# Board2.net
KiCad netlist of a schematic drawn in EAGLE
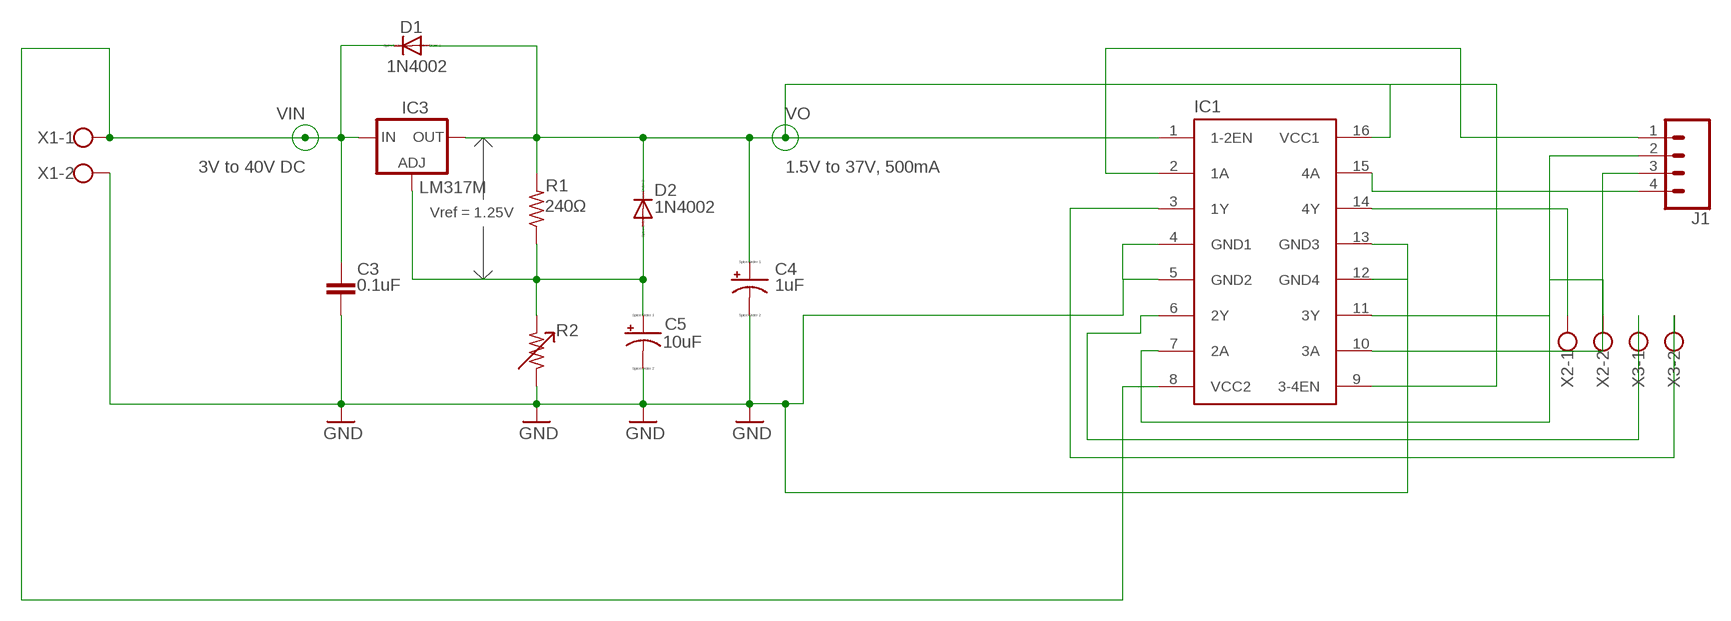
[diagram p0: schematic, sheet 1]

(export (version "E")
  (design (tool "Eeschema 10.0.6"))
  (components
    (comp (ref "C3")
      (value "0.1uF")
      (footprint "eagle-import:C075-052X106")
      (libsource (lib "eagle-import") (part "C-EU075-052X106"))
    )
    (comp (ref "C4")
      (value "1uF")
      (footprint "eagle-import:085CS_1AR")
      (libsource (lib "eagle-import") (part "CPOL-US085CS-1AR"))
    )
    (comp (ref "C5")
      (value "10uF")
      (footprint "eagle-import:085CS_1AR")
      (libsource (lib "eagle-import") (part "CPOL-US085CS-1AR"))
    )
    (comp (ref "D1")
      (value "1N4002")
      (footprint "eagle-import:DO41-10")
      (libsource (lib "eagle-import") (part "1N4004"))
    )
    (comp (ref "D2")
      (value "1N4002")
      (footprint "eagle-import:DO41-10")
      (libsource (lib "eagle-import") (part "1N4004"))
    )
    (comp (ref "IC1")
      (value "L293D")
      (footprint "eagle-import:DIL16")
      (libsource (lib "eagle-import") (part "L293D"))
    )
    (comp (ref "IC3")
      (value "LM317MBSTT3")
      (footprint "eagle-import:SOT223")
      (fields (field (name "PARTNUMBER") "LM317M"))
      (libsource (lib "eagle-import") (part "LM317?MBSTT3"))
    )
    (comp (ref "J1")
      (value "CONN_04PTH")
      (footprint "eagle-import:1X04")
      (libsource (lib "eagle-import") (part "CONN_04PTH"))
    )
    (comp (ref "R1")
      (value "240Ω")
      (footprint "eagle-import:M0805")
      (libsource (lib "eagle-import") (part "R-US_M0805"))
    )
    (comp (ref "R2")
      (value "RESISTOR_TRIMR0805")
      (footprint "eagle-import:R0805")
      (libsource (lib "eagle-import") (part "RESISTOR_TRIMR0805"))
    )
    (comp (ref "X1")
      (value "W237-102")
      (footprint "eagle-import:W237-102")
      (fields (field (name "MPN") "237-102"))
      (libsource (lib "eagle-import") (part "W237-102"))
    )
    (comp (ref "X2")
      (value "W237-102")
      (footprint "eagle-import:W237-102")
      (fields (field (name "MPN") "237-102"))
      (libsource (lib "eagle-import") (part "W237-102"))
    )
    (comp (ref "X3")
      (value "W237-102")
      (footprint "eagle-import:W237-102")
      (fields (field (name "MPN") "237-102"))
      (libsource (lib "eagle-import") (part "W237-102"))
    )
  )
  (nets
    (net (code "1") (name "/VIN") (class "Default")
      (node (ref "C3") (pin "1") (pinfunction "1_1") (pintype "passive"))
      (node (ref "D1") (pin "C") (pinfunction "C_C") (pintype "passive"))
      (node (ref "IC1") (pin "8") (pinfunction "VCC2_8") (pintype "power_in"))
      (node (ref "IC3") (pin "3") (pinfunction "IN_3") (pintype "input"))
      (node (ref "X1") (pin "1") (pinfunction "KL_1") (pintype "passive"))
    )
    (net (code "2") (name "/VO") (class "Default")
      (node (ref "C4") (pin "+") (pinfunction "+_+") (pintype "passive"))
      (node (ref "D1") (pin "A") (pinfunction "A_A") (pintype "passive"))
      (node (ref "D2") (pin "C") (pinfunction "C_C") (pintype "passive"))
      (node (ref "IC1") (pin "1") (pinfunction "1-2EN_1") (pintype "input"))
      (node (ref "IC1") (pin "16") (pinfunction "VCC1_16") (pintype "power_in"))
      (node (ref "IC1") (pin "9") (pinfunction "3-4EN_9") (pintype "input"))
      (node (ref "IC3") (pin "4") (pinfunction "OUT_4") (pintype "passive"))
      (node (ref "R1") (pin "2") (pinfunction "2_2") (pintype "passive"))
    )
    (net (code "3") (name "GND") (class "Default")
      (node (ref "C3") (pin "2") (pinfunction "2_2") (pintype "passive"))
      (node (ref "C4") (pin "-") (pinfunction "-_-") (pintype "passive"))
      (node (ref "C5") (pin "-") (pinfunction "-_-") (pintype "passive"))
      (node (ref "IC1") (pin "12") (pinfunction "GND4_12") (pintype "power_in"))
      (node (ref "IC1") (pin "13") (pinfunction "GND3_13") (pintype "power_in"))
      (node (ref "IC1") (pin "4") (pinfunction "GND1_4") (pintype "power_in"))
      (node (ref "IC1") (pin "5") (pinfunction "GND2_5") (pintype "power_in"))
      (node (ref "R2") (pin "1") (pinfunction "1_1") (pintype "passive"))
      (node (ref "X1") (pin "2") (pinfunction "KL_2") (pintype "passive"))
    )
    (net (code "4") (name "Net-(IC1-1A)") (class "Default")
      (node (ref "IC1") (pin "2") (pinfunction "1A_2") (pintype "input"))
      (node (ref "J1") (pin "1") (pinfunction "1_1") (pintype "passive"))
    )
    (net (code "5") (name "Net-(IC1-1Y)") (class "Default")
      (node (ref "IC1") (pin "3") (pinfunction "1Y_3") (pintype "output"))
      (node (ref "X3") (pin "2") (pinfunction "KL_2") (pintype "passive"))
    )
    (net (code "6") (name "Net-(IC1-2A)") (class "Default")
      (node (ref "IC1") (pin "7") (pinfunction "2A_7") (pintype "input"))
      (node (ref "J1") (pin "2") (pinfunction "2_2") (pintype "passive"))
    )
    (net (code "7") (name "Net-(IC1-2Y)") (class "Default")
      (node (ref "IC1") (pin "6") (pinfunction "2Y_6") (pintype "output"))
      (node (ref "X3") (pin "1") (pinfunction "KL_1") (pintype "passive"))
    )
    (net (code "8") (name "Net-(IC1-3A)") (class "Default")
      (node (ref "IC1") (pin "10") (pinfunction "3A_10") (pintype "input"))
      (node (ref "J1") (pin "3") (pinfunction "3_3") (pintype "passive"))
    )
    (net (code "9") (name "Net-(IC1-3Y)") (class "Default")
      (node (ref "IC1") (pin "11") (pinfunction "3Y_11") (pintype "output"))
      (node (ref "X2") (pin "2") (pinfunction "KL_2") (pintype "passive"))
    )
    (net (code "10") (name "Net-(IC1-4A)") (class "Default")
      (node (ref "IC1") (pin "15") (pinfunction "4A_15") (pintype "input"))
      (node (ref "J1") (pin "4") (pinfunction "4_4") (pintype "passive"))
    )
    (net (code "11") (name "Net-(IC1-4Y)") (class "Default")
      (node (ref "IC1") (pin "14") (pinfunction "4Y_14") (pintype "output"))
      (node (ref "X2") (pin "1") (pinfunction "KL_1") (pintype "passive"))
    )
    (net (code "12") (name "Net-(IC3-ADJ)") (class "Default")
      (node (ref "C5") (pin "+") (pinfunction "+_+") (pintype "passive"))
      (node (ref "D2") (pin "A") (pinfunction "A_A") (pintype "passive"))
      (node (ref "IC3") (pin "1") (pinfunction "ADJ_1") (pintype "input"))
      (node (ref "R1") (pin "1") (pinfunction "1_1") (pintype "passive"))
      (node (ref "R2") (pin "2") (pinfunction "2_2") (pintype "passive"))
    )
  )
)
